# imu.net
KiCad netlist of a schematic drawn in EAGLE
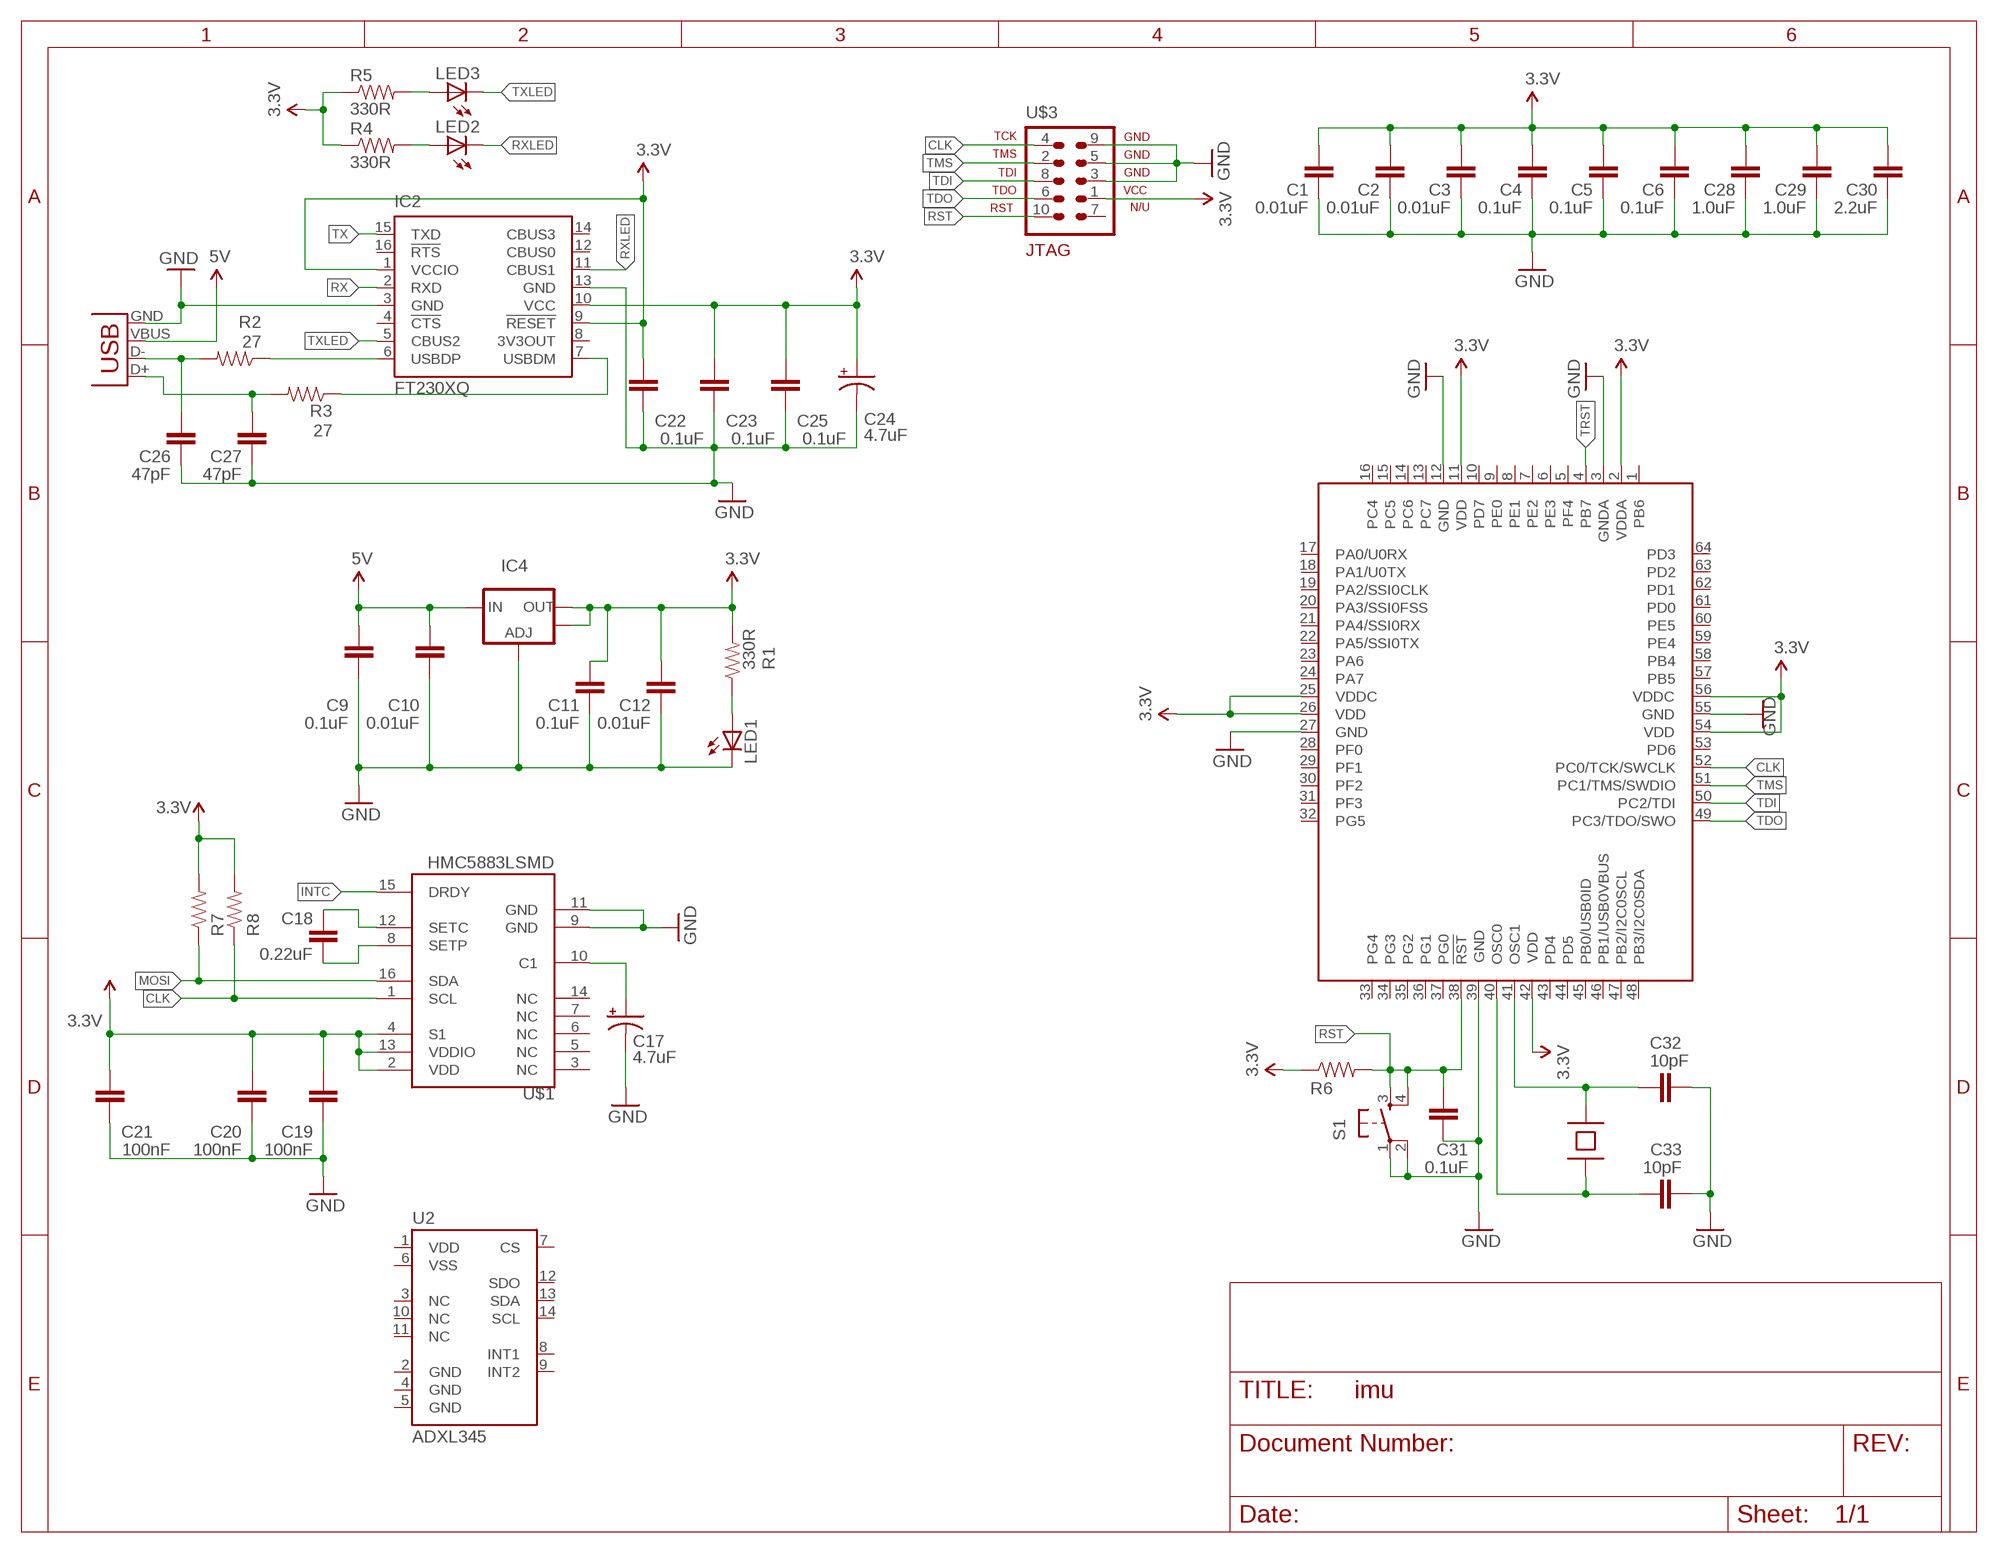
[diagram p0: schematic, sheet 1]

(export (version "E")
  (design (tool "Eeschema 10.0.6"))
  (components
    (comp (ref "C1")
      (value "0.01uF")
      (footprint "eagle-import:0603-CAP")
      (libsource (lib "eagle-import") (part "CAP0603-CAP"))
    )
    (comp (ref "C2")
      (value "0.01uF")
      (footprint "eagle-import:0603-CAP")
      (libsource (lib "eagle-import") (part "CAP0603-CAP"))
    )
    (comp (ref "C3")
      (value "0.01uF")
      (footprint "eagle-import:0603-CAP")
      (libsource (lib "eagle-import") (part "CAP0603-CAP"))
    )
    (comp (ref "C4")
      (value "0.1uF")
      (footprint "eagle-import:0603-CAP")
      (libsource (lib "eagle-import") (part "CAP0603-CAP"))
    )
    (comp (ref "C5")
      (value "0.1uF")
      (footprint "eagle-import:0603-CAP")
      (libsource (lib "eagle-import") (part "CAP0603-CAP"))
    )
    (comp (ref "C6")
      (value "0.1uF")
      (footprint "eagle-import:0603-CAP")
      (libsource (lib "eagle-import") (part "CAP0603-CAP"))
    )
    (comp (ref "C9")
      (value "0.1uF")
      (footprint "eagle-import:0603-CAP")
      (libsource (lib "eagle-import") (part "CAP0603-CAP"))
    )
    (comp (ref "C10")
      (value "0.01uF")
      (footprint "eagle-import:0603-CAP")
      (libsource (lib "eagle-import") (part "CAP0603-CAP"))
    )
    (comp (ref "C11")
      (value "0.1uF")
      (footprint "eagle-import:0603-CAP")
      (libsource (lib "eagle-import") (part "CAP0603-CAP"))
    )
    (comp (ref "C12")
      (value "0.01uF")
      (footprint "eagle-import:0603-CAP")
      (libsource (lib "eagle-import") (part "CAP0603-CAP"))
    )
    (comp (ref "C17")
      (value "4.7uF")
      (footprint "eagle-import:EIA3216")
      (libsource (lib "eagle-import") (part "CAP_POL1206"))
    )
    (comp (ref "C18")
      (value "0.22uF")
      (footprint "eagle-import:0603-CAP")
      (libsource (lib "eagle-import") (part "CAP0603-CAP"))
    )
    (comp (ref "C19")
      (value "100nF")
      (footprint "eagle-import:0603-CAP")
      (libsource (lib "eagle-import") (part "CAP0603-CAP"))
    )
    (comp (ref "C20")
      (value "100nF")
      (footprint "eagle-import:0603-CAP")
      (libsource (lib "eagle-import") (part "CAP0603-CAP"))
    )
    (comp (ref "C21")
      (value "100nF")
      (footprint "eagle-import:0603-CAP")
      (libsource (lib "eagle-import") (part "CAP0603-CAP"))
    )
    (comp (ref "C22")
      (value "0.1uF")
      (footprint "eagle-import:0603-CAP")
      (libsource (lib "eagle-import") (part "CAP0603-CAP"))
    )
    (comp (ref "C23")
      (value "0.1uF")
      (footprint "eagle-import:0603-CAP")
      (libsource (lib "eagle-import") (part "CAP0603-CAP"))
    )
    (comp (ref "C24")
      (value "4.7uF")
      (footprint "eagle-import:EIA3216")
      (libsource (lib "eagle-import") (part "CAP_POL1206"))
    )
    (comp (ref "C25")
      (value "0.1uF")
      (footprint "eagle-import:0603-CAP")
      (libsource (lib "eagle-import") (part "CAP0603-CAP"))
    )
    (comp (ref "C26")
      (value "47pF")
      (footprint "eagle-import:0603-CAP")
      (libsource (lib "eagle-import") (part "CAP0603-CAP"))
    )
    (comp (ref "C27")
      (value "47pF")
      (footprint "eagle-import:0603-CAP")
      (libsource (lib "eagle-import") (part "CAP0603-CAP"))
    )
    (comp (ref "C28")
      (value "1.0uF")
      (footprint "eagle-import:0603-CAP")
      (libsource (lib "eagle-import") (part "CAP0603-CAP"))
    )
    (comp (ref "C29")
      (value "1.0uF")
      (footprint "eagle-import:0603-CAP")
      (libsource (lib "eagle-import") (part "CAP0603-CAP"))
    )
    (comp (ref "C30")
      (value "2.2uF")
      (footprint "eagle-import:0603-CAP")
      (libsource (lib "eagle-import") (part "CAP0603-CAP"))
    )
    (comp (ref "C31")
      (value "0.1uF")
      (footprint "eagle-import:0603-CAP")
      (libsource (lib "eagle-import") (part "CAP0603-CAP"))
    )
    (comp (ref "C32")
      (value "10pF")
      (footprint "eagle-import:0603-CAP")
      (libsource (lib "eagle-import") (part "CAP0603-CAP"))
    )
    (comp (ref "C33")
      (value "10pF")
      (footprint "eagle-import:0603-CAP")
      (libsource (lib "eagle-import") (part "CAP0603-CAP"))
    )
    (comp (ref "IC1")
      (value "TM4C123[6,F]XXPM")
      (footprint "eagle-import:PM_S-PQFP-G64")
      (libsource (lib "eagle-import") (part "TM4C123[6,F]XXPM"))
    )
    (comp (ref "IC2")
      (value "FT230XQ")
      (footprint "eagle-import:QFN16")
      (libsource (lib "eagle-import") (part "FT230XQ"))
    )
    (comp (ref "IC4")
      (value "V_REG_LM1117SOT223")
      (footprint "eagle-import:SOT223")
      (libsource (lib "eagle-import") (part "V_REG_LM1117SOT223"))
    )
    (comp (ref "JP1")
      (value "USBSMD")
      (footprint "eagle-import:USB-MINIB")
      (libsource (lib "eagle-import") (part "USBSMD"))
    )
    (comp (ref "LED1")
      (value "LED0603")
      (footprint "eagle-import:LED-0603")
      (libsource (lib "eagle-import") (part "LED0603"))
    )
    (comp (ref "LED2")
      (value "LED0603")
      (footprint "eagle-import:LED-0603")
      (libsource (lib "eagle-import") (part "LED0603"))
    )
    (comp (ref "LED3")
      (value "LED0603")
      (footprint "eagle-import:LED-0603")
      (libsource (lib "eagle-import") (part "LED0603"))
    )
    (comp (ref "R1")
      (value "330R")
      (footprint "eagle-import:0805")
      (libsource (lib "eagle-import") (part "RESISTOR0805-RES"))
    )
    (comp (ref "R2")
      (value "27")
      (footprint "eagle-import:0603-RES")
      (libsource (lib "eagle-import") (part "RESISTOR0603-RES"))
    )
    (comp (ref "R3")
      (value "27")
      (footprint "eagle-import:0603-RES")
      (libsource (lib "eagle-import") (part "RESISTOR0603-RES"))
    )
    (comp (ref "R4")
      (value "330R")
      (footprint "eagle-import:0603-RES")
      (libsource (lib "eagle-import") (part "RESISTOR0603-RES"))
    )
    (comp (ref "R5")
      (value "330R")
      (footprint "eagle-import:0603-RES")
      (libsource (lib "eagle-import") (part "RESISTOR0603-RES"))
    )
    (comp (ref "R6")
      (value "RESISTOR0603-RES")
      (footprint "eagle-import:0603-RES")
      (libsource (lib "eagle-import") (part "RESISTOR0603-RES"))
    )
    (comp (ref "R7")
      (value "RESISTOR0603-RES")
      (footprint "eagle-import:0603-RES")
      (libsource (lib "eagle-import") (part "RESISTOR0603-RES"))
    )
    (comp (ref "R8")
      (value "RESISTOR0603-RES")
      (footprint "eagle-import:0603-RES")
      (libsource (lib "eagle-import") (part "RESISTOR0603-RES"))
    )
    (comp (ref "S1")
      (value "TAC_SWITCHSMD")
      (footprint "eagle-import:TACTILE_SWITCH_SMD")
      (libsource (lib "eagle-import") (part "TAC_SWITCHSMD"))
    )
    (comp (ref "U$1")
      (value "HMC5883LSMD")
      (footprint "eagle-import:16LPCC")
      (libsource (lib "eagle-import") (part "HMC5883LSMD"))
    )
    (comp (ref "U$2")
      (value "SMDCRYSTAL3225")
      (footprint "eagle-import:IQG3225")
      (libsource (lib "eagle-import") (part "SMDCRYSTAL3225"))
    )
    (comp (ref "U$3")
      (value "ARM10JTAG")
      (footprint "eagle-import:AVR-JTAG-10")
      (libsource (lib "eagle-import") (part "ARM10JTAG"))
    )
    (comp (ref "U2")
      (value "ADXL345")
      (footprint "eagle-import:LGA14")
      (libsource (lib "eagle-import") (part "ADXL345"))
    )
  )
  (nets
    (net (code "1") (name "3.3V") (class "Default")
      (node (ref "C1") (pin "2") (pinfunction "2_2") (pintype "passive"))
      (node (ref "C11") (pin "2") (pinfunction "2_2") (pintype "passive"))
      (node (ref "C12") (pin "2") (pinfunction "2_2") (pintype "passive"))
      (node (ref "C19") (pin "2") (pinfunction "2_2") (pintype "passive"))
      (node (ref "C2") (pin "2") (pinfunction "2_2") (pintype "passive"))
      (node (ref "C20") (pin "2") (pinfunction "2_2") (pintype "passive"))
      (node (ref "C21") (pin "2") (pinfunction "2_2") (pintype "passive"))
      (node (ref "C22") (pin "2") (pinfunction "2_2") (pintype "passive"))
      (node (ref "C23") (pin "2") (pinfunction "2_2") (pintype "passive"))
      (node (ref "C24") (pin "A") (pinfunction "+_A") (pintype "passive"))
      (node (ref "C25") (pin "2") (pinfunction "2_2") (pintype "passive"))
      (node (ref "C28") (pin "2") (pinfunction "2_2") (pintype "passive"))
      (node (ref "C29") (pin "2") (pinfunction "2_2") (pintype "passive"))
      (node (ref "C3") (pin "2") (pinfunction "2_2") (pintype "passive"))
      (node (ref "C30") (pin "2") (pinfunction "2_2") (pintype "passive"))
      (node (ref "C4") (pin "2") (pinfunction "2_2") (pintype "passive"))
      (node (ref "C5") (pin "2") (pinfunction "2_2") (pintype "passive"))
      (node (ref "C6") (pin "2") (pinfunction "2_2") (pintype "passive"))
      (node (ref "IC1") (pin "11") (pinfunction "VDD_11") (pintype "bidirectional"))
      (node (ref "IC1") (pin "2") (pinfunction "VDDA_2") (pintype "bidirectional"))
      (node (ref "IC1") (pin "25") (pinfunction "VDDC_25") (pintype "bidirectional"))
      (node (ref "IC1") (pin "26") (pinfunction "VDD_26") (pintype "bidirectional"))
      (node (ref "IC1") (pin "42") (pinfunction "VDD_42") (pintype "bidirectional"))
      (node (ref "IC1") (pin "54") (pinfunction "VDD_54") (pintype "bidirectional"))
      (node (ref "IC1") (pin "56") (pinfunction "VDDC_56") (pintype "bidirectional"))
      (node (ref "IC2") (pin "1") (pinfunction "VCCIO_1") (pintype "power_in"))
      (node (ref "IC2") (pin "10") (pinfunction "VCC_10") (pintype "power_in"))
      (node (ref "IC2") (pin "9") (pinfunction "~{RESET}_9") (pintype "input"))
      (node (ref "IC4") (pin "2") (pinfunction "OUT_2") (pintype "passive"))
      (node (ref "IC4") (pin "4") (pinfunction "OUT_4") (pintype "passive"))
      (node (ref "R1") (pin "2") (pinfunction "2_2") (pintype "passive"))
      (node (ref "R4") (pin "1") (pinfunction "1_1") (pintype "passive"))
      (node (ref "R5") (pin "1") (pinfunction "1_1") (pintype "passive"))
      (node (ref "R6") (pin "1") (pinfunction "1_1") (pintype "passive"))
      (node (ref "R7") (pin "2") (pinfunction "2_2") (pintype "passive"))
      (node (ref "R8") (pin "2") (pinfunction "2_2") (pintype "passive"))
      (node (ref "U$1") (pin "13") (pinfunction "VDDIO_13") (pintype "bidirectional"))
      (node (ref "U$1") (pin "2") (pinfunction "VDD_2") (pintype "bidirectional"))
      (node (ref "U$1") (pin "4") (pinfunction "S1_4") (pintype "bidirectional"))
      (node (ref "U$3") (pin "1") (pinfunction "1_1") (pintype "passive"))
    )
    (net (code "2") (name "5V") (class "Default")
      (node (ref "C10") (pin "2") (pinfunction "2_2") (pintype "passive"))
      (node (ref "C9") (pin "2") (pinfunction "2_2") (pintype "passive"))
      (node (ref "IC4") (pin "3") (pinfunction "IN_3") (pintype "input"))
      (node (ref "JP1") (pin "VBUS") (pinfunction "VBUS_VBUS") (pintype "bidirectional"))
    )
    (net (code "3") (name "CLK") (class "Default")
      (node (ref "IC1") (pin "52") (pinfunction "PC0/TCK/SWCLK_52") (pintype "bidirectional"))
      (node (ref "R8") (pin "1") (pinfunction "1_1") (pintype "passive"))
      (node (ref "U$1") (pin "1") (pinfunction "SCL_1") (pintype "bidirectional"))
      (node (ref "U$3") (pin "4") (pinfunction "4_4") (pintype "passive"))
    )
    (net (code "4") (name "GND") (class "Default")
      (node (ref "C1") (pin "1") (pinfunction "1_1") (pintype "passive"))
      (node (ref "C10") (pin "1") (pinfunction "1_1") (pintype "passive"))
      (node (ref "C11") (pin "1") (pinfunction "1_1") (pintype "passive"))
      (node (ref "C12") (pin "1") (pinfunction "1_1") (pintype "passive"))
      (node (ref "C17") (pin "C") (pinfunction "-_C") (pintype "passive"))
      (node (ref "C19") (pin "1") (pinfunction "1_1") (pintype "passive"))
      (node (ref "C2") (pin "1") (pinfunction "1_1") (pintype "passive"))
      (node (ref "C20") (pin "1") (pinfunction "1_1") (pintype "passive"))
      (node (ref "C21") (pin "1") (pinfunction "1_1") (pintype "passive"))
      (node (ref "C22") (pin "1") (pinfunction "1_1") (pintype "passive"))
      (node (ref "C23") (pin "1") (pinfunction "1_1") (pintype "passive"))
      (node (ref "C24") (pin "C") (pinfunction "-_C") (pintype "passive"))
      (node (ref "C25") (pin "1") (pinfunction "1_1") (pintype "passive"))
      (node (ref "C26") (pin "1") (pinfunction "1_1") (pintype "passive"))
      (node (ref "C27") (pin "1") (pinfunction "1_1") (pintype "passive"))
      (node (ref "C28") (pin "1") (pinfunction "1_1") (pintype "passive"))
      (node (ref "C29") (pin "1") (pinfunction "1_1") (pintype "passive"))
      (node (ref "C3") (pin "1") (pinfunction "1_1") (pintype "passive"))
      (node (ref "C30") (pin "1") (pinfunction "1_1") (pintype "passive"))
      (node (ref "C31") (pin "1") (pinfunction "1_1") (pintype "passive"))
      (node (ref "C32") (pin "1") (pinfunction "1_1") (pintype "passive"))
      (node (ref "C33") (pin "2") (pinfunction "2_2") (pintype "passive"))
      (node (ref "C4") (pin "1") (pinfunction "1_1") (pintype "passive"))
      (node (ref "C5") (pin "1") (pinfunction "1_1") (pintype "passive"))
      (node (ref "C6") (pin "1") (pinfunction "1_1") (pintype "passive"))
      (node (ref "C9") (pin "1") (pinfunction "1_1") (pintype "passive"))
      (node (ref "IC1") (pin "12") (pinfunction "GND_12") (pintype "bidirectional"))
      (node (ref "IC1") (pin "27") (pinfunction "GND_27") (pintype "bidirectional"))
      (node (ref "IC1") (pin "3") (pinfunction "GNDA_3") (pintype "bidirectional"))
      (node (ref "IC1") (pin "39") (pinfunction "GND_39") (pintype "bidirectional"))
      (node (ref "IC1") (pin "55") (pinfunction "GND_55") (pintype "bidirectional"))
      (node (ref "IC2") (pin "13") (pinfunction "GND_13") (pintype "power_in"))
      (node (ref "IC2") (pin "3") (pinfunction "GND_3") (pintype "power_in"))
      (node (ref "IC4") (pin "1") (pinfunction "ADJ_1") (pintype "input"))
      (node (ref "JP1") (pin "GND") (pinfunction "GND_GND") (pintype "bidirectional"))
      (node (ref "LED1") (pin "C") (pinfunction "C_C") (pintype "passive"))
      (node (ref "S1") (pin "1") (pinfunction "1_1") (pintype "passive"))
      (node (ref "S1") (pin "2") (pinfunction "2_2") (pintype "passive"))
      (node (ref "U$1") (pin "11") (pinfunction "GND_11") (pintype "bidirectional"))
      (node (ref "U$1") (pin "9") (pinfunction "GND_9") (pintype "bidirectional"))
      (node (ref "U$3") (pin "3") (pinfunction "3_3") (pintype "passive"))
      (node (ref "U$3") (pin "5") (pinfunction "5_5") (pintype "passive"))
      (node (ref "U$3") (pin "9") (pinfunction "9_9") (pintype "passive"))
    )
    (net (code "5") (name "INTC") (class "Default")
      (node (ref "U$1") (pin "15") (pinfunction "DRDY_15") (pintype "bidirectional"))
    )
    (net (code "6") (name "MOSI") (class "Default")
      (node (ref "R7") (pin "1") (pinfunction "1_1") (pintype "passive"))
      (node (ref "U$1") (pin "16") (pinfunction "SDA_16") (pintype "bidirectional"))
    )
    (net (code "7") (name "Net-(C17-+)") (class "Default")
      (node (ref "C17") (pin "A") (pinfunction "+_A") (pintype "passive"))
      (node (ref "U$1") (pin "10") (pinfunction "C1_10") (pintype "bidirectional"))
    )
    (net (code "8") (name "Net-(C26-Pad2)") (class "Default")
      (node (ref "C26") (pin "2") (pinfunction "2_2") (pintype "passive"))
      (node (ref "JP1") (pin "D-") (pinfunction "D-_D-") (pintype "bidirectional"))
      (node (ref "R2") (pin "2") (pinfunction "2_2") (pintype "passive"))
    )
    (net (code "9") (name "Net-(C27-Pad2)") (class "Default")
      (node (ref "C27") (pin "2") (pinfunction "2_2") (pintype "passive"))
      (node (ref "JP1") (pin "D+") (pinfunction "D+_D+") (pintype "bidirectional"))
      (node (ref "R3") (pin "2") (pinfunction "2_2") (pintype "passive"))
    )
    (net (code "10") (name "Net-(IC1-OSC0)") (class "Default")
      (node (ref "C33") (pin "1") (pinfunction "1_1") (pintype "passive"))
      (node (ref "IC1") (pin "40") (pinfunction "OSC0_40") (pintype "bidirectional"))
      (node (ref "U$2") (pin "1") (pinfunction "P$1_1") (pintype "bidirectional"))
    )
    (net (code "11") (name "Net-(IC1-OSC1)") (class "Default")
      (node (ref "C32") (pin "2") (pinfunction "2_2") (pintype "passive"))
      (node (ref "IC1") (pin "41") (pinfunction "OSC1_41") (pintype "bidirectional"))
      (node (ref "U$2") (pin "3") (pinfunction "P$2_3") (pintype "bidirectional"))
    )
    (net (code "12") (name "Net-(IC2-USBDM)") (class "Default")
      (node (ref "IC2") (pin "7") (pinfunction "USBDM_7") (pintype "input"))
      (node (ref "R3") (pin "1") (pinfunction "1_1") (pintype "passive"))
    )
    (net (code "13") (name "Net-(IC2-USBDP)") (class "Default")
      (node (ref "IC2") (pin "6") (pinfunction "USBDP_6") (pintype "input"))
      (node (ref "R2") (pin "1") (pinfunction "1_1") (pintype "passive"))
    )
    (net (code "14") (name "Net-(LED1-PadA)") (class "Default")
      (node (ref "LED1") (pin "A") (pinfunction "A_A") (pintype "passive"))
      (node (ref "R1") (pin "1") (pinfunction "1_1") (pintype "passive"))
    )
    (net (code "15") (name "Net-(LED2-PadA)") (class "Default")
      (node (ref "LED2") (pin "A") (pinfunction "A_A") (pintype "passive"))
      (node (ref "R4") (pin "2") (pinfunction "2_2") (pintype "passive"))
    )
    (net (code "16") (name "Net-(LED3-PadA)") (class "Default")
      (node (ref "LED3") (pin "A") (pinfunction "A_A") (pintype "passive"))
      (node (ref "R5") (pin "2") (pinfunction "2_2") (pintype "passive"))
    )
    (net (code "17") (name "Net-(U$1-SETC)") (class "Default")
      (node (ref "C18") (pin "2") (pinfunction "2_2") (pintype "passive"))
      (node (ref "U$1") (pin "12") (pinfunction "SETC_12") (pintype "bidirectional"))
    )
    (net (code "18") (name "Net-(U$1-SETP)") (class "Default")
      (node (ref "C18") (pin "1") (pinfunction "1_1") (pintype "passive"))
      (node (ref "U$1") (pin "8") (pinfunction "SETP_8") (pintype "bidirectional"))
    )
    (net (code "19") (name "RST") (class "Default")
      (node (ref "C31") (pin "2") (pinfunction "2_2") (pintype "passive"))
      (node (ref "IC1") (pin "38") (pinfunction "~{RST}_38") (pintype "bidirectional"))
      (node (ref "R6") (pin "2") (pinfunction "2_2") (pintype "passive"))
      (node (ref "S1") (pin "3") (pinfunction "3_3") (pintype "passive"))
      (node (ref "S1") (pin "4") (pinfunction "4_4") (pintype "passive"))
      (node (ref "U$3") (pin "10") (pinfunction "10_10") (pintype "passive"))
    )
    (net (code "20") (name "RX") (class "Default")
      (node (ref "IC2") (pin "2") (pinfunction "RXD_2") (pintype "input"))
    )
    (net (code "21") (name "RXLED") (class "Default")
      (node (ref "IC2") (pin "11") (pinfunction "CBUS1_11") (pintype "bidirectional"))
      (node (ref "LED2") (pin "C") (pinfunction "C_C") (pintype "passive"))
    )
    (net (code "22") (name "TDI") (class "Default")
      (node (ref "IC1") (pin "50") (pinfunction "PC2/TDI_50") (pintype "bidirectional"))
      (node (ref "U$3") (pin "8") (pinfunction "8_8") (pintype "passive"))
    )
    (net (code "23") (name "TDO") (class "Default")
      (node (ref "IC1") (pin "49") (pinfunction "PC3/TDO/SWO_49") (pintype "bidirectional"))
      (node (ref "U$3") (pin "6") (pinfunction "6_6") (pintype "passive"))
    )
    (net (code "24") (name "TMS") (class "Default")
      (node (ref "IC1") (pin "51") (pinfunction "PC1/TMS/SWDIO_51") (pintype "bidirectional"))
      (node (ref "U$3") (pin "2") (pinfunction "2_2") (pintype "passive"))
    )
    (net (code "25") (name "TRST") (class "Default")
      (node (ref "IC1") (pin "4") (pinfunction "PB7_4") (pintype "bidirectional"))
    )
    (net (code "26") (name "TX") (class "Default")
      (node (ref "IC2") (pin "15") (pinfunction "TXD_15") (pintype "output"))
    )
    (net (code "27") (name "TXLED") (class "Default")
      (node (ref "IC2") (pin "5") (pinfunction "CBUS2_5") (pintype "bidirectional"))
      (node (ref "LED3") (pin "C") (pinfunction "C_C") (pintype "passive"))
    )
    (net (code "28") (name "unconnected-(IC1-PA0{slash}U0RX-Pad17)") (class "Default")
      (node (ref "IC1") (pin "17") (pinfunction "PA0/U0RX_17") (pintype "bidirectional"))
    )
    (net (code "29") (name "unconnected-(IC1-PA1{slash}U0TX-Pad18)") (class "Default")
      (node (ref "IC1") (pin "18") (pinfunction "PA1/U0TX_18") (pintype "bidirectional"))
    )
    (net (code "30") (name "unconnected-(IC1-PA2{slash}SSI0CLK-Pad19)") (class "Default")
      (node (ref "IC1") (pin "19") (pinfunction "PA2/SSI0CLK_19") (pintype "bidirectional"))
    )
    (net (code "31") (name "unconnected-(IC1-PA3{slash}SSI0FSS-Pad20)") (class "Default")
      (node (ref "IC1") (pin "20") (pinfunction "PA3/SSI0FSS_20") (pintype "bidirectional"))
    )
    (net (code "32") (name "unconnected-(IC1-PA4{slash}SSI0RX-Pad21)") (class "Default")
      (node (ref "IC1") (pin "21") (pinfunction "PA4/SSI0RX_21") (pintype "bidirectional"))
    )
    (net (code "33") (name "unconnected-(IC1-PA5{slash}SSI0TX-Pad22)") (class "Default")
      (node (ref "IC1") (pin "22") (pinfunction "PA5/SSI0TX_22") (pintype "bidirectional"))
    )
    (net (code "34") (name "unconnected-(IC1-PA6-Pad23)") (class "Default")
      (node (ref "IC1") (pin "23") (pinfunction "PA6_23") (pintype "bidirectional"))
    )
    (net (code "35") (name "unconnected-(IC1-PA7-Pad24)") (class "Default")
      (node (ref "IC1") (pin "24") (pinfunction "PA7_24") (pintype "bidirectional"))
    )
    (net (code "36") (name "unconnected-(IC1-PB0{slash}USB0ID-Pad45)") (class "Default")
      (node (ref "IC1") (pin "45") (pinfunction "PB0/USB0ID_45") (pintype "bidirectional"))
    )
    (net (code "37") (name "unconnected-(IC1-PB1{slash}USB0VBUS-Pad46)") (class "Default")
      (node (ref "IC1") (pin "46") (pinfunction "PB1/USB0VBUS_46") (pintype "bidirectional"))
    )
    (net (code "38") (name "unconnected-(IC1-PB2{slash}I2C0SCL-Pad47)") (class "Default")
      (node (ref "IC1") (pin "47") (pinfunction "PB2/I2C0SCL_47") (pintype "bidirectional"))
    )
    (net (code "39") (name "unconnected-(IC1-PB3{slash}I2C0SDA-Pad48)") (class "Default")
      (node (ref "IC1") (pin "48") (pinfunction "PB3/I2C0SDA_48") (pintype "bidirectional"))
    )
    (net (code "40") (name "unconnected-(IC1-PB4-Pad58)") (class "Default")
      (node (ref "IC1") (pin "58") (pinfunction "PB4_58") (pintype "bidirectional"))
    )
    (net (code "41") (name "unconnected-(IC1-PB5-Pad57)") (class "Default")
      (node (ref "IC1") (pin "57") (pinfunction "PB5_57") (pintype "bidirectional"))
    )
    (net (code "42") (name "unconnected-(IC1-PB6-Pad1)") (class "Default")
      (node (ref "IC1") (pin "1") (pinfunction "PB6_1") (pintype "bidirectional"))
    )
    (net (code "43") (name "unconnected-(IC1-PC4-Pad16)") (class "Default")
      (node (ref "IC1") (pin "16") (pinfunction "PC4_16") (pintype "bidirectional"))
    )
    (net (code "44") (name "unconnected-(IC1-PC5-Pad15)") (class "Default")
      (node (ref "IC1") (pin "15") (pinfunction "PC5_15") (pintype "bidirectional"))
    )
    (net (code "45") (name "unconnected-(IC1-PC6-Pad14)") (class "Default")
      (node (ref "IC1") (pin "14") (pinfunction "PC6_14") (pintype "bidirectional"))
    )
    (net (code "46") (name "unconnected-(IC1-PC7-Pad13)") (class "Default")
      (node (ref "IC1") (pin "13") (pinfunction "PC7_13") (pintype "bidirectional"))
    )
    (net (code "47") (name "unconnected-(IC1-PD0-Pad61)") (class "Default")
      (node (ref "IC1") (pin "61") (pinfunction "PD0_61") (pintype "bidirectional"))
    )
    (net (code "48") (name "unconnected-(IC1-PD1-Pad62)") (class "Default")
      (node (ref "IC1") (pin "62") (pinfunction "PD1_62") (pintype "bidirectional"))
    )
    (net (code "49") (name "unconnected-(IC1-PD2-Pad63)") (class "Default")
      (node (ref "IC1") (pin "63") (pinfunction "PD2_63") (pintype "bidirectional"))
    )
    (net (code "50") (name "unconnected-(IC1-PD3-Pad64)") (class "Default")
      (node (ref "IC1") (pin "64") (pinfunction "PD3_64") (pintype "bidirectional"))
    )
    (net (code "51") (name "unconnected-(IC1-PD4-Pad43)") (class "Default")
      (node (ref "IC1") (pin "43") (pinfunction "PD4_43") (pintype "bidirectional"))
    )
    (net (code "52") (name "unconnected-(IC1-PD5-Pad44)") (class "Default")
      (node (ref "IC1") (pin "44") (pinfunction "PD5_44") (pintype "bidirectional"))
    )
    (net (code "53") (name "unconnected-(IC1-PD6-Pad53)") (class "Default")
      (node (ref "IC1") (pin "53") (pinfunction "PD6_53") (pintype "bidirectional"))
    )
    (net (code "54") (name "unconnected-(IC1-PD7-Pad10)") (class "Default")
      (node (ref "IC1") (pin "10") (pinfunction "PD7_10") (pintype "bidirectional"))
    )
    (net (code "55") (name "unconnected-(IC1-PE0-Pad9)") (class "Default")
      (node (ref "IC1") (pin "9") (pinfunction "PE0_9") (pintype "bidirectional"))
    )
    (net (code "56") (name "unconnected-(IC1-PE1-Pad8)") (class "Default")
      (node (ref "IC1") (pin "8") (pinfunction "PE1_8") (pintype "bidirectional"))
    )
    (net (code "57") (name "unconnected-(IC1-PE2-Pad7)") (class "Default")
      (node (ref "IC1") (pin "7") (pinfunction "PE2_7") (pintype "bidirectional"))
    )
    (net (code "58") (name "unconnected-(IC1-PE3-Pad6)") (class "Default")
      (node (ref "IC1") (pin "6") (pinfunction "PE3_6") (pintype "bidirectional"))
    )
    (net (code "59") (name "unconnected-(IC1-PE4-Pad59)") (class "Default")
      (node (ref "IC1") (pin "59") (pinfunction "PE4_59") (pintype "bidirectional"))
    )
    (net (code "60") (name "unconnected-(IC1-PE5-Pad60)") (class "Default")
      (node (ref "IC1") (pin "60") (pinfunction "PE5_60") (pintype "bidirectional"))
    )
    (net (code "61") (name "unconnected-(IC1-PF0-Pad28)") (class "Default")
      (node (ref "IC1") (pin "28") (pinfunction "PF0_28") (pintype "bidirectional"))
    )
    (net (code "62") (name "unconnected-(IC1-PF1-Pad29)") (class "Default")
      (node (ref "IC1") (pin "29") (pinfunction "PF1_29") (pintype "bidirectional"))
    )
    (net (code "63") (name "unconnected-(IC1-PF2-Pad30)") (class "Default")
      (node (ref "IC1") (pin "30") (pinfunction "PF2_30") (pintype "bidirectional"))
    )
    (net (code "64") (name "unconnected-(IC1-PF3-Pad31)") (class "Default")
      (node (ref "IC1") (pin "31") (pinfunction "PF3_31") (pintype "bidirectional"))
    )
    (net (code "65") (name "unconnected-(IC1-PF4-Pad5)") (class "Default")
      (node (ref "IC1") (pin "5") (pinfunction "PF4_5") (pintype "bidirectional"))
    )
    (net (code "66") (name "unconnected-(IC1-PG0-Pad37)") (class "Default")
      (node (ref "IC1") (pin "37") (pinfunction "PG0_37") (pintype "bidirectional"))
    )
    (net (code "67") (name "unconnected-(IC1-PG1-Pad36)") (class "Default")
      (node (ref "IC1") (pin "36") (pinfunction "PG1_36") (pintype "bidirectional"))
    )
    (net (code "68") (name "unconnected-(IC1-PG2-Pad35)") (class "Default")
      (node (ref "IC1") (pin "35") (pinfunction "PG2_35") (pintype "bidirectional"))
    )
    (net (code "69") (name "unconnected-(IC1-PG3-Pad34)") (class "Default")
      (node (ref "IC1") (pin "34") (pinfunction "PG3_34") (pintype "bidirectional"))
    )
    (net (code "70") (name "unconnected-(IC1-PG4-Pad33)") (class "Default")
      (node (ref "IC1") (pin "33") (pinfunction "PG4_33") (pintype "bidirectional"))
    )
    (net (code "71") (name "unconnected-(IC1-PG5-Pad32)") (class "Default")
      (node (ref "IC1") (pin "32") (pinfunction "PG5_32") (pintype "bidirectional"))
    )
    (net (code "72") (name "unconnected-(IC2-3V3OUT-Pad8)") (class "Default")
      (node (ref "IC2") (pin "8") (pinfunction "3V3OUT_8") (pintype "output"))
    )
    (net (code "73") (name "unconnected-(IC2-CBUS0-Pad12)") (class "Default")
      (node (ref "IC2") (pin "12") (pinfunction "CBUS0_12") (pintype "bidirectional"))
    )
    (net (code "74") (name "unconnected-(IC2-CBUS3-Pad14)") (class "Default")
      (node (ref "IC2") (pin "14") (pinfunction "CBUS3_14") (pintype "bidirectional"))
    )
    (net (code "75") (name "unconnected-(IC2-~{CTS}-Pad4)") (class "Default")
      (node (ref "IC2") (pin "4") (pinfunction "~{CTS}_4") (pintype "input"))
    )
    (net (code "76") (name "unconnected-(IC2-~{RTS}-Pad16)") (class "Default")
      (node (ref "IC2") (pin "16") (pinfunction "~{RTS}_16") (pintype "output"))
    )
    (net (code "77") (name "unconnected-(U$1-NC-Pad3)") (class "Default")
      (node (ref "U$1") (pin "3") (pinfunction "NC_3") (pintype "bidirectional"))
    )
    (net (code "78") (name "unconnected-(U$1-NC-Pad5)") (class "Default")
      (node (ref "U$1") (pin "5") (pinfunction "NC_5") (pintype "bidirectional"))
    )
    (net (code "79") (name "unconnected-(U$1-NC-Pad6)") (class "Default")
      (node (ref "U$1") (pin "6") (pinfunction "NC_6") (pintype "bidirectional"))
    )
    (net (code "80") (name "unconnected-(U$1-NC-Pad7)") (class "Default")
      (node (ref "U$1") (pin "7") (pinfunction "NC_7") (pintype "bidirectional"))
    )
    (net (code "81") (name "unconnected-(U$1-NC-Pad14)") (class "Default")
      (node (ref "U$1") (pin "14") (pinfunction "NC_14") (pintype "bidirectional"))
    )
    (net (code "82") (name "unconnected-(U$3-Pad7)") (class "Default")
      (node (ref "U$3") (pin "7") (pinfunction "7_7") (pintype "passive"))
    )
    (net (code "83") (name "unconnected-(U2-CS-Pad7)") (class "Default")
      (node (ref "U2") (pin "7") (pinfunction "CS_7") (pintype "bidirectional"))
    )
    (net (code "84") (name "unconnected-(U2-GND-Pad2)") (class "Default")
      (node (ref "U2") (pin "2") (pinfunction "GND_2") (pintype "bidirectional"))
    )
    (net (code "85") (name "unconnected-(U2-GND-Pad4)") (class "Default")
      (node (ref "U2") (pin "4") (pinfunction "GND_4") (pintype "bidirectional"))
    )
    (net (code "86") (name "unconnected-(U2-GND-Pad5)") (class "Default")
      (node (ref "U2") (pin "5") (pinfunction "GND_5") (pintype "bidirectional"))
    )
    (net (code "87") (name "unconnected-(U2-INT1-Pad8)") (class "Default")
      (node (ref "U2") (pin "8") (pinfunction "INT1_8") (pintype "bidirectional"))
    )
    (net (code "88") (name "unconnected-(U2-INT2-Pad9)") (class "Default")
      (node (ref "U2") (pin "9") (pinfunction "INT2_9") (pintype "bidirectional"))
    )
    (net (code "89") (name "unconnected-(U2-NC-Pad3)") (class "Default")
      (node (ref "U2") (pin "3") (pinfunction "NC_3") (pintype "bidirectional"))
    )
    (net (code "90") (name "unconnected-(U2-NC-Pad10)") (class "Default")
      (node (ref "U2") (pin "10") (pinfunction "NC_10") (pintype "bidirectional"))
    )
    (net (code "91") (name "unconnected-(U2-NC-Pad11)") (class "Default")
      (node (ref "U2") (pin "11") (pinfunction "NC_11") (pintype "bidirectional"))
    )
    (net (code "92") (name "unconnected-(U2-SCL-Pad14)") (class "Default")
      (node (ref "U2") (pin "14") (pinfunction "SCL_14") (pintype "bidirectional"))
    )
    (net (code "93") (name "unconnected-(U2-SDA-Pad13)") (class "Default")
      (node (ref "U2") (pin "13") (pinfunction "SDA_13") (pintype "bidirectional"))
    )
    (net (code "94") (name "unconnected-(U2-SDO-Pad12)") (class "Default")
      (node (ref "U2") (pin "12") (pinfunction "SDO_12") (pintype "bidirectional"))
    )
    (net (code "95") (name "unconnected-(U2-VDD-Pad1)") (class "Default")
      (node (ref "U2") (pin "1") (pinfunction "VDD_1") (pintype "bidirectional"))
    )
    (net (code "96") (name "unconnected-(U2-VSS-Pad6)") (class "Default")
      (node (ref "U2") (pin "6") (pinfunction "VSS_6") (pintype "bidirectional"))
    )
  )
)
